# nfc-epd-power.net
KiCad netlist of a schematic drawn in Altium Designer
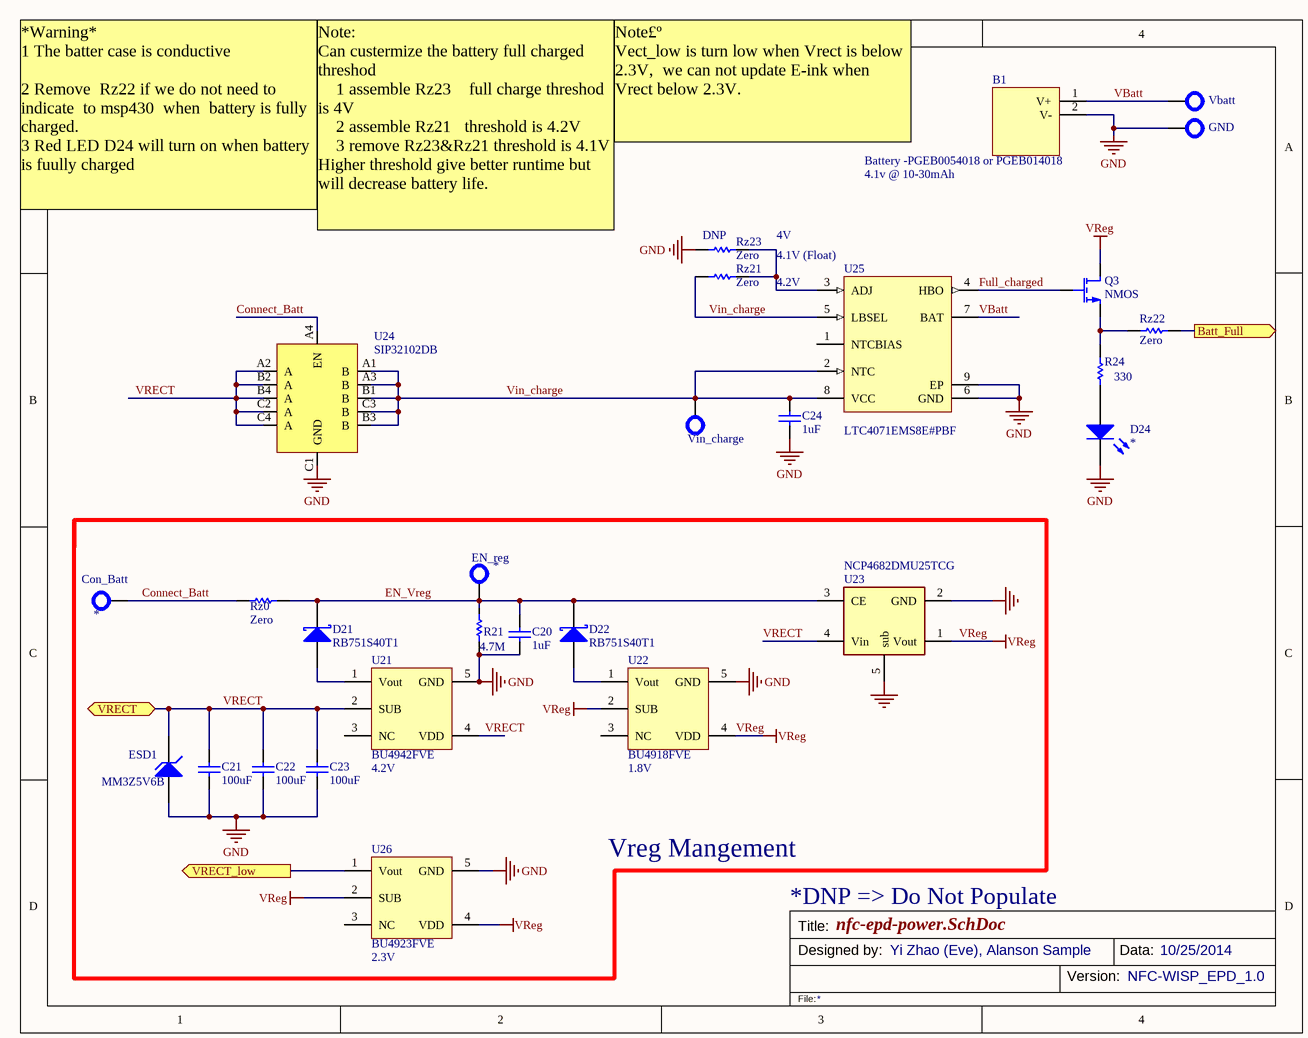
[diagram p0: nfc-epd-power.SchDoc]

(export (version "E")
  (design (tool "Eeschema 10.0.6"))
  (components
    (comp (ref "B1")
      (value "Battery -PGEB0054018 or PGEB014018")
      (footprint "Battery -PGEB0054018-Pad_only")
      (description "ThinFilm solid state battery  - 4.1V 1.0MAH")
      (fields
        (field (name "MANUFACTURER PART NUMBER") "MEC201-10S (several in same formfactor)")
        (field (name "MANUFACTURER") "Infinite Power Solutions")
        (field (name "ALTIUM_VALUE") "4.1v @ 10-30mAh")
      )
      (libsource (lib "WISP_AD10") (part "Battery - MEC201"))
    )
    (comp (ref "C20")
      (value "1uF")
      (footprint "0603")
      (description "Ceramic Capacitor (Surface Mount)")
      (fields (field (name "MANUFACTURER") "Generic Ceramic Chip Cap (TBD)") (field (name "Comment") "Cap"))
      (libsource (lib "WISP_AD10") (part "Cap"))
    )
    (comp (ref "C21")
      (value "100uF")
      (footprint "1206")
      (description "Ceramic Capacitor (Surface Mount)")
      (fields (field (name "MANUFACTURER") "Generic Ceramic Chip Cap (TBD)") (field (name "Comment") "Cap"))
      (libsource (lib "WISP_AD10") (part "Cap"))
    )
    (comp (ref "C22")
      (value "100uF")
      (footprint "1206")
      (description "Ceramic Capacitor (Surface Mount)")
      (fields (field (name "MANUFACTURER") "Generic Ceramic Chip Cap (TBD)") (field (name "Comment") "Cap"))
      (libsource (lib "WISP_AD10") (part "Cap"))
    )
    (comp (ref "C23")
      (value "100uF")
      (footprint "1206")
      (description "Ceramic Capacitor (Surface Mount)")
      (fields (field (name "MANUFACTURER") "Generic Ceramic Chip Cap (TBD)") (field (name "Comment") "Cap"))
      (libsource (lib "WISP_AD10") (part "Cap"))
    )
    (comp (ref "C24")
      (value "1uF")
      (footprint "0603")
      (description "Ceramic Capacitor (Surface Mount)")
      (fields (field (name "MANUFACTURER") "Generic Ceramic Chip Cap (TBD)") (field (name "Comment") "Cap"))
      (libsource (lib "WISP_AD10") (part "Cap"))
    )
    (comp (ref "Con_Batt")
      (value "Test Point")
      (footprint "Test Point - Super Small")
      (description "Test Point, large or small foot prints")
      (fields
        (field (name "DIGI-KEY PART NUMBER") "Example: 5000K-ND, 5012K-ND, Surface mount 5015KCT-ND")
        (field (name "MANUFACTURER PART NUMBER") "Example: 5000, 5013")
        (field (name "NOTE") "*")
      )
      (libsource (lib "WISP_AD10") (part "Test Point"))
    )
    (comp (ref "D21")
      (value "RB751S40T1")
      (footprint "SOD-523")
      (description "Schottky Diode")
      (fields (field (name "PUBLISHER") "Altium Limited"))
      (libsource (lib "WISP_AD10") (part "RB751S40T1"))
    )
    (comp (ref "D22")
      (value "RB751S40T1")
      (footprint "SOD-523")
      (description "Schottky Diode")
      (fields (field (name "PUBLISHER") "Altium Limited"))
      (libsource (lib "WISP_AD10") (part "RB751S40T1"))
    )
    (comp (ref "D24")
      (value "LED")
      (footprint "Diode - 0603")
      (description "Typical RED, GREEN, YELLOW, AMBER GaAs LED")
      (fields (field (name "ALTIUM_VALUE") "*"))
      (libsource (lib "WISP_AD10") (part "Diode - LED"))
    )
    (comp (ref "EN_reg")
      (value "Test Point")
      (footprint "Test Point - Small")
      (description "Test Point, large or small foot prints")
      (fields
        (field (name "DIGI-KEY PART NUMBER") "Example: 5000K-ND, 5012K-ND, Surface mount 5015KCT-ND")
        (field (name "MANUFACTURER PART NUMBER") "Example: 5000, 5013")
        (field (name "NOTE") "*")
      )
      (libsource (lib "WISP_AD10") (part "Test Point"))
    )
    (comp (ref "ESD1")
      (value "MM3Z5V6B")
      (footprint "SOD-323")
      (description "Vz=5.6V, Overvoltage Protection Zener")
      (fields (field (name "MANUFACTURER") "Fairchild") (field (name "DIGI-KEY PART NUMBER") "MM3Z5V6BCT-ND"))
      (libsource (lib "WISP_AD10") (part "MM3Z4V3B"))
    )
    (comp (ref "GND1")
      (value "GND")
      (footprint "Test Point - Super Small")
      (description "Test Point, large or small foot prints")
      (fields
        (field (name "DIGI-KEY PART NUMBER") "Example: 5000K-ND, 5012K-ND, Surface mount 5015KCT-ND")
        (field (name "MANUFACTURER PART NUMBER") "Example: 5000, 5013")
      )
      (libsource (lib "WISP_AD10") (part "Test Point"))
    )
    (comp (ref "Q3")
      (value "NMOS")
      (footprint "SOT-323 / SC-70")
      (description "N-Channel MOSFET")
      (libsource (lib "WISP_AD10") (part "MOSFET-N"))
    )
    (comp (ref "R21")
      (value "4.7M")
      (footprint "0603")
      (description "Chip Resistor (Surface Mount)")
      (fields (field (name "MANUFACTURER") "Generic Chip Res (TBD)") (field (name "Comment") "Res"))
      (libsource (lib "WREL_AD10") (part "Res"))
    )
    (comp (ref "R24")
      (value "330")
      (footprint "0603")
      (description "Chip Resistor (Surface Mount)")
      (fields (field (name "MANUFACTURER") "Generic Chip Res (TBD)") (field (name "Comment") "Res"))
      (libsource (lib "WISP_AD10") (part "Res"))
    )
    (comp (ref "Rz0")
      (value "Zero")
      (footprint "0603")
      (description "Chip Resistor (Surface Mount)")
      (fields
        (field (name "MANUFACTURER") "Generic Chip Res (TBD)")
        (field (name "MANUFACTURER PART NUMBER") "RC0603FR-070RL")
      )
      (libsource (lib "WREL_AD10") (part "Res"))
    )
    (comp (ref "Rz21")
      (value "Zero")
      (footprint "0603")
      (description "Chip Resistor (Surface Mount)")
      (fields
        (field (name "MANUFACTURER") "Generic Chip Res (TBD)")
        (field (name "MANUFACTURER PART NUMBER") "RC0603FR-070RL")
      )
      (libsource (lib "WREL_AD10") (part "Res"))
    )
    (comp (ref "Rz22")
      (value "Zero")
      (footprint "0603")
      (description "Chip Resistor (Surface Mount)")
      (fields
        (field (name "MANUFACTURER") "Generic Chip Res (TBD)")
        (field (name "MANUFACTURER PART NUMBER") "RC0603FR-070RL")
      )
      (libsource (lib "WREL_AD10") (part "Res"))
    )
    (comp (ref "Rz23")
      (value "Zero")
      (footprint "0603")
      (description "Chip Resistor (Surface Mount)")
      (fields
        (field (name "MANUFACTURER") "Generic Chip Res (TBD)")
        (field (name "MANUFACTURER PART NUMBER") "RC0603FR-070RL")
        (field (name "NOTE") "DNP")
      )
      (libsource (lib "WREL_AD10") (part "Res"))
    )
    (comp (ref "U21")
      (value "BU4942FVE")
      (footprint "VSOF5/SOT665")
      (description "VSOF-5,Supervisor")
      (fields (field (name "ALTIUM_VALUE") "4.2V"))
      (libsource (lib "WISP_AD10") (part "BU49xxFVE"))
    )
    (comp (ref "U22")
      (value "BU4918FVE")
      (footprint "VSOF5/SOT665")
      (description "VSOF-5,Supervisor")
      (fields (field (name "ALTIUM_VALUE") "1.8V"))
      (libsource (lib "WISP_AD10") (part "BU49xxFVE"))
    )
    (comp (ref "U23")
      (value "NCP4682DMU25TCG")
      (footprint "4-UDFN")
      (description "Regulator: LDO  NCP4682 (with enable), 4-UDFN package")
      (fields
        (field (name "DIGI-KEY PART NUMBER") "NCP4682DMU25TCGOSCT-ND")
        (field (name "MANUFACTURER") "ON Semiconductor")
      )
      (libsource (lib "WISP_AD10") (part "NCP4682DMU25TCG"))
    )
    (comp (ref "U24")
      (value "SIP32102DB")
      (footprint "WCSP-12")
      (description "Bi-directional Load Switch")
      (libsource (lib "WISP_AD10") (part "SIP32102DB"))
    )
    (comp (ref "U25")
      (value "LTC4071EMS8E#PBF")
      (footprint "LT-MS8E-8-1880X1680TP_N")
      (fields (field (name "MANUFACTURER") "Linear Technology"))
      (libsource (lib "Linear Technology Power Management Energy Harvesting") (part "LTC4071EMS8E#PBF"))
    )
    (comp (ref "U26")
      (value "BU4923FVE")
      (footprint "VSOF5/SOT665")
      (description "VSOF-5,Supervisor")
      (fields (field (name "VAULE") "2.3V"))
      (libsource (lib "WISP_AD10") (part "BU49xxFVE"))
    )
    (comp (ref "Vbatt")
      (value "Vbatt")
      (footprint "Test Point - Super Small")
      (description "Test Point, large or small foot prints")
      (fields
        (field (name "DIGI-KEY PART NUMBER") "Example: 5000K-ND, 5012K-ND, Surface mount 5015KCT-ND")
        (field (name "MANUFACTURER PART NUMBER") "Example: 5000, 5013")
      )
      (libsource (lib "WISP_AD10") (part "Test Point"))
    )
    (comp (ref "Vin_charge")
      (value "Test Point")
      (footprint "Test Point - Super Small")
      (description "Test Point, large or small foot prints")
      (fields
        (field (name "DIGI-KEY PART NUMBER") "Example: 5000K-ND, 5012K-ND, Surface mount 5015KCT-ND")
        (field (name "MANUFACTURER PART NUMBER") "Example: 5000, 5013")
      )
      (libsource (lib "WISP_AD10") (part "Test Point"))
    )
  )
  (nets
    (net (code "2") (name "/Batt_Full") (class "Default")
      (node (ref "Rz22") (pin "1") (pinfunction "1_1") (pintype "passive"))
    )
    (net (code "3") (name "/Connect_Batt") (class "Default")
      (node (ref "Con_Batt") (pin "0") (pinfunction "0_0") (pintype "passive"))
      (node (ref "Rz0") (pin "2") (pinfunction "2_2") (pintype "passive"))
      (node (ref "U24") (pin "A4") (pinfunction "EN_A4") (pintype "passive"))
    )
    (net (code "4") (name "/EN_Vreg") (class "Default")
      (node (ref "C20") (pin "2") (pinfunction "2_2") (pintype "passive"))
      (node (ref "D21") (pin "2") (pinfunction "C_2") (pintype "passive"))
      (node (ref "D22") (pin "2") (pinfunction "C_2") (pintype "passive"))
      (node (ref "EN_reg") (pin "0") (pinfunction "0_0") (pintype "passive"))
      (node (ref "R21") (pin "2") (pinfunction "2_2") (pintype "passive"))
      (node (ref "Rz0") (pin "1") (pinfunction "1_1") (pintype "passive"))
      (node (ref "U23") (pin "3") (pinfunction "CE_3") (pintype "passive"))
    )
    (net (code "5") (name "/Full_charged") (class "Default")
      (node (ref "Q3") (pin "1") (pinfunction "G_1") (pintype "passive"))
      (node (ref "U25") (pin "4") (pinfunction "HBO_4") (pintype "output"))
    )
    (net (code "6") (name "/VBatt") (class "Default")
      (node (ref "B1") (pin "1") (pinfunction "V+_1") (pintype "passive"))
      (node (ref "U25") (pin "7") (pinfunction "BAT_7") (pintype "power_in"))
      (node (ref "Vbatt") (pin "0") (pinfunction "0_0") (pintype "passive"))
    )
    (net (code "7") (name "/VRECT") (class "Default")
      (node (ref "C21") (pin "2") (pinfunction "2_2") (pintype "passive"))
      (node (ref "C22") (pin "2") (pinfunction "2_2") (pintype "passive"))
      (node (ref "C23") (pin "2") (pinfunction "2_2") (pintype "passive"))
      (node (ref "ESD1") (pin "2") (pinfunction "C_2") (pintype "passive"))
      (node (ref "U21") (pin "2") (pinfunction "SUB_2") (pintype "passive"))
      (node (ref "U21") (pin "4") (pinfunction "VDD_4") (pintype "passive"))
      (node (ref "U23") (pin "4") (pinfunction "Vin_4") (pintype "passive"))
      (node (ref "U24") (pin "A2") (pinfunction "A_A2") (pintype "power_in"))
      (node (ref "U24") (pin "B2") (pinfunction "A_B2") (pintype "passive"))
      (node (ref "U24") (pin "B4") (pinfunction "A_B4") (pintype "passive"))
      (node (ref "U24") (pin "C2") (pinfunction "A_C2") (pintype "passive"))
      (node (ref "U24") (pin "C4") (pinfunction "A_C4") (pintype "passive"))
    )
    (net (code "8") (name "/VRECT_low") (class "Default")
      (node (ref "U26") (pin "1") (pinfunction "Vout_1") (pintype "passive"))
    )
    (net (code "9") (name "/Vin_charge") (class "Default")
      (node (ref "C24") (pin "2") (pinfunction "2_2") (pintype "passive"))
      (node (ref "Rz21") (pin "2") (pinfunction "2_2") (pintype "passive"))
      (node (ref "U24") (pin "A1") (pinfunction "B_A1") (pintype "passive"))
      (node (ref "U24") (pin "A3") (pinfunction "B_A3") (pintype "power_in"))
      (node (ref "U24") (pin "B1") (pinfunction "B_B1") (pintype "passive"))
      (node (ref "U24") (pin "B3") (pinfunction "B_B3") (pintype "passive"))
      (node (ref "U24") (pin "C3") (pinfunction "B_C3") (pintype "passive"))
      (node (ref "U25") (pin "2") (pinfunction "NTC_2") (pintype "input"))
      (node (ref "U25") (pin "5") (pinfunction "LBSEL_5") (pintype "input"))
      (node (ref "U25") (pin "8") (pinfunction "VCC_8") (pintype "power_in"))
      (node (ref "Vin_charge") (pin "0") (pinfunction "0_0") (pintype "passive"))
    )
    (net (code "10") (name "GND") (class "Default")
      (node (ref "B1") (pin "2") (pinfunction "V-_2") (pintype "passive"))
      (node (ref "C20") (pin "1") (pinfunction "1_1") (pintype "passive"))
      (node (ref "C21") (pin "1") (pinfunction "1_1") (pintype "passive"))
      (node (ref "C22") (pin "1") (pinfunction "1_1") (pintype "passive"))
      (node (ref "C23") (pin "1") (pinfunction "1_1") (pintype "passive"))
      (node (ref "C24") (pin "1") (pinfunction "1_1") (pintype "passive"))
      (node (ref "D24") (pin "2") (pinfunction "K_2") (pintype "passive"))
      (node (ref "ESD1") (pin "1") (pinfunction "A_1") (pintype "passive"))
      (node (ref "GND1") (pin "0") (pinfunction "0_0") (pintype "passive"))
      (node (ref "R21") (pin "1") (pinfunction "1_1") (pintype "passive"))
      (node (ref "Rz23") (pin "2") (pinfunction "2_2") (pintype "passive"))
      (node (ref "U21") (pin "5") (pinfunction "GND_5") (pintype "passive"))
      (node (ref "U22") (pin "5") (pinfunction "GND_5") (pintype "passive"))
      (node (ref "U23") (pin "2") (pinfunction "GND_2") (pintype "passive"))
      (node (ref "U23") (pin "5") (pinfunction "sub_5") (pintype "passive"))
      (node (ref "U24") (pin "C1") (pinfunction "GND_C1") (pintype "passive"))
      (node (ref "U25") (pin "6") (pinfunction "GND_6") (pintype "power_in"))
      (node (ref "U25") (pin "9") (pinfunction "EP_9") (pintype "power_in"))
      (node (ref "U26") (pin "5") (pinfunction "GND_5") (pintype "passive"))
    )
    (net (code "11") (name "Net-(D21-A)") (class "Default")
      (node (ref "D21") (pin "1") (pinfunction "A_1") (pintype "passive"))
      (node (ref "U21") (pin "1") (pinfunction "Vout_1") (pintype "passive"))
    )
    (net (code "12") (name "Net-(D22-A)") (class "Default")
      (node (ref "D22") (pin "1") (pinfunction "A_1") (pintype "passive"))
      (node (ref "U22") (pin "1") (pinfunction "Vout_1") (pintype "passive"))
    )
    (net (code "13") (name "Net-(D24-A)") (class "Default")
      (node (ref "D24") (pin "1") (pinfunction "A_1") (pintype "passive"))
      (node (ref "R24") (pin "2") (pinfunction "2_2") (pintype "passive"))
    )
    (net (code "14") (name "Net-(Q3-S)") (class "Default")
      (node (ref "Q3") (pin "2") (pinfunction "S_2") (pintype "passive"))
      (node (ref "R24") (pin "1") (pinfunction "1_1") (pintype "passive"))
      (node (ref "Rz22") (pin "2") (pinfunction "2_2") (pintype "passive"))
    )
    (net (code "15") (name "Net-(U25-ADJ)") (class "Default")
      (node (ref "Rz21") (pin "1") (pinfunction "1_1") (pintype "passive"))
      (node (ref "Rz23") (pin "1") (pinfunction "1_1") (pintype "passive"))
      (node (ref "U25") (pin "3") (pinfunction "ADJ_3") (pintype "input"))
    )
    (net (code "16") (name "VReg") (class "Default")
      (node (ref "Q3") (pin "3") (pinfunction "D_3") (pintype "passive"))
      (node (ref "U22") (pin "2") (pinfunction "SUB_2") (pintype "passive"))
      (node (ref "U22") (pin "4") (pinfunction "VDD_4") (pintype "passive"))
      (node (ref "U23") (pin "1") (pinfunction "Vout_1") (pintype "power_in"))
      (node (ref "U26") (pin "2") (pinfunction "SUB_2") (pintype "passive"))
      (node (ref "U26") (pin "4") (pinfunction "VDD_4") (pintype "passive"))
    )
    (net (code "17") (name "unconnected-(U21-NC-Pad3)") (class "Default")
      (node (ref "U21") (pin "3") (pinfunction "NC_3") (pintype "tri_state"))
    )
    (net (code "18") (name "unconnected-(U22-NC-Pad3)") (class "Default")
      (node (ref "U22") (pin "3") (pinfunction "NC_3") (pintype "tri_state"))
    )
    (net (code "19") (name "unconnected-(U25-NTCBIAS-Pad1)") (class "Default")
      (node (ref "U25") (pin "1") (pinfunction "NTCBIAS_1") (pintype "passive"))
    )
    (net (code "20") (name "unconnected-(U26-NC-Pad3)") (class "Default")
      (node (ref "U26") (pin "3") (pinfunction "NC_3") (pintype "tri_state"))
    )
  )
)
